# Clocks.net
KiCad netlist of a schematic drawn in Altium Designer
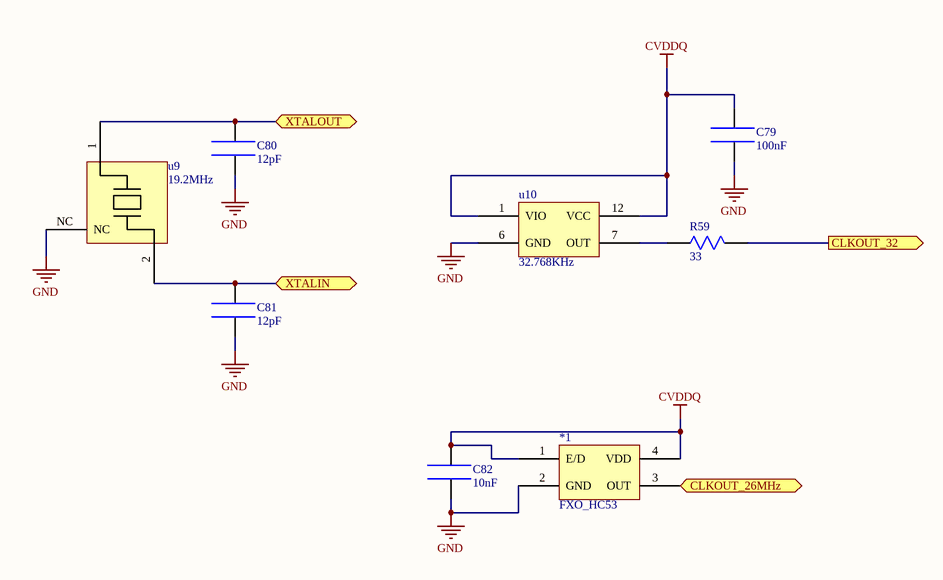
[diagram p0: Clocks.SchDoc]

(export (version "E")
  (design (tool "Eeschema 10.0.6"))
  (components
    (comp (ref "*1")
      (value "FXO_HC53")
      (footprint "FXO_HC53")
      (libsource (lib "DA_Component_Library") (part "FXO_HC53"))
    )
    (comp (ref "C79")
      (value "100nF")
      (footprint "SMD Capacitor 0603")
      (fields (field (name "Comment") "Capacitor"))
      (libsource (lib "DA_Component_Library") (part "Capacitor"))
    )
    (comp (ref "C80")
      (value "12pF")
      (footprint "SMD Capacitor 0603")
      (fields (field (name "Comment") "Capacitor"))
      (libsource (lib "DA_Component_Library") (part "Capacitor"))
    )
    (comp (ref "C81")
      (value "12pF")
      (footprint "SMD Capacitor 0603")
      (fields (field (name "Comment") "Capacitor"))
      (libsource (lib "DA_Component_Library") (part "Capacitor"))
    )
    (comp (ref "C82")
      (value "10nF")
      (footprint "SMD Capacitor 0603")
      (fields (field (name "Comment") "Capacitor"))
      (libsource (lib "DA_Component_Library") (part "Capacitor"))
    )
    (comp (ref "R59")
      (value "33")
      (footprint "SMD Resistor 0603")
      (fields (field (name "Comment") "Resistor"))
      (libsource (lib "DA_Component_Library") (part "Resistor"))
    )
    (comp (ref "u9")
      (value "CrystalOSC_General")
      (footprint "NX3225SA")
      (fields (field (name "FREQ") "19.2MHz"))
      (libsource (lib "DA_Component_Library") (part "CrystalOSC_General"))
    )
    (comp (ref "u10")
      (value "SG-3040LC")
      (footprint "SG-3040LC")
      (fields (field (name "FREQ") "32.768KHz"))
      (libsource (lib "DA_Component_Library") (part "SG-3040LC"))
    )
  )
  (nets
    (net (code "1") (name "/CLKOUT_26MHz") (class "Default")
      (node (ref "*1") (pin "3") (pinfunction "OUT_3") (pintype "passive"))
    )
    (net (code "2") (name "/CLKOUT_32") (class "Default")
      (node (ref "R59") (pin "1") (pinfunction "1_1") (pintype "passive"))
    )
    (net (code "3") (name "/XTALIN") (class "Default")
      (node (ref "C81") (pin "1") (pinfunction "1_1") (pintype "passive"))
      (node (ref "u9") (pin "2") (pinfunction "2_2") (pintype "passive"))
    )
    (net (code "4") (name "/XTALOUT") (class "Default")
      (node (ref "C80") (pin "1") (pinfunction "1_1") (pintype "passive"))
      (node (ref "u9") (pin "1") (pinfunction "1_1") (pintype "passive"))
    )
    (net (code "5") (name "CVDDQ") (class "Default")
      (node (ref "*1") (pin "1") (pinfunction "E/D_1") (pintype "passive"))
      (node (ref "*1") (pin "4") (pinfunction "VDD_4") (pintype "passive"))
      (node (ref "C79") (pin "1") (pinfunction "1_1") (pintype "passive"))
      (node (ref "C82") (pin "1") (pinfunction "1_1") (pintype "passive"))
      (node (ref "u10") (pin "1") (pinfunction "VIO_1") (pintype "passive"))
      (node (ref "u10") (pin "12") (pinfunction "VCC_12") (pintype "passive"))
    )
    (net (code "6") (name "GND") (class "Default")
      (node (ref "*1") (pin "2") (pinfunction "GND_2") (pintype "passive"))
      (node (ref "C79") (pin "0") (pinfunction "0_0") (pintype "passive"))
      (node (ref "C80") (pin "0") (pinfunction "0_0") (pintype "passive"))
      (node (ref "C81") (pin "0") (pinfunction "0_0") (pintype "passive"))
      (node (ref "C82") (pin "0") (pinfunction "0_0") (pintype "passive"))
      (node (ref "u10") (pin "6") (pinfunction "GND_6") (pintype "passive"))
      (node (ref "u9") (pin "NC") (pinfunction "NC_NC") (pintype "passive"))
    )
    (net (code "7") (name "Net-(u10-OUT)") (class "Default")
      (node (ref "R59") (pin "0") (pinfunction "0_0") (pintype "passive"))
      (node (ref "u10") (pin "7") (pinfunction "OUT_7") (pintype "passive"))
    )
  )
)
